# USB.net
KiCad netlist of a schematic drawn in Altium Designer
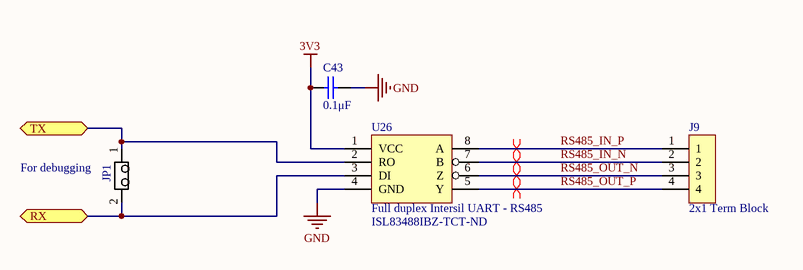
[diagram p0: USB.SchDoc]

(export (version "E")
  (design (tool "Eeschema 10.0.6"))
  (components
    (comp (ref "C43")
      (value "0.1μF")
      (footprint "CAPC1608N(0603\")")
      (description "Capacitor, Ceramic, 100V, +/- 10%, 0603 SMD, X7R")
      (fields
        (field (name "MFG") "TDK")
        (field (name "PUBLISHER") "AUVic")
        (field (name "CREATED BY") "Ashwin Sira")
      )
      (libsource (lib "AUVic_Integrated_Library_Capacitors") (part "0.1uF 100V 0603 SMD, Ceramic"))
    )
    (comp (ref "J9")
      (value "2x1 Term Block")
      (footprint "4X1 Terminal Block")
      (fields (field (name "MADE BY") "Andy Bates"))
      (libsource (lib "AUVic_Integrated_Library_Connectors") (part "4x1 Terminal Block"))
    )
    (comp (ref "JP1")
      (value "1X2 Pin Head")
      (footprint "2X1 Males Header")
      (fields (field (name "MADE BY") "Andy Bates"))
      (libsource (lib "AUVic_Schematic_Library_Connectors") (part "1x2 Male Header"))
    )
    (comp (ref "U26")
      (value "Full duplex Intersil UART - RS485")
      (footprint "SOIC-SN8_M")
      (fields
        (field (name "SUPPLIER PART NUMBER 1") "ISL83488IBZ-TCT-ND")
        (field (name "MADE BY") "Andy Bates")
      )
      (libsource (lib "AUVic_Integrated_Library_Interface") (part "Full duplex Intersil UART - RS485"))
    )
  )
  (nets
    (net (code "1") (name "/RS485_IN_N") (class "Default")
      (node (ref "J9") (pin "2") (pinfunction "2_2") (pintype "passive"))
      (node (ref "U26") (pin "7") (pinfunction "B_7") (pintype "passive"))
    )
    (net (code "2") (name "/RS485_IN_P") (class "Default")
      (node (ref "J9") (pin "1") (pinfunction "1_1") (pintype "passive"))
      (node (ref "U26") (pin "8") (pinfunction "A_8") (pintype "passive"))
    )
    (net (code "3") (name "/RS485_OUT_N") (class "Default")
      (node (ref "J9") (pin "3") (pinfunction "3_3") (pintype "passive"))
      (node (ref "U26") (pin "6") (pinfunction "Z_6") (pintype "passive"))
    )
    (net (code "4") (name "/RS485_OUT_P") (class "Default")
      (node (ref "J9") (pin "4") (pinfunction "4_4") (pintype "passive"))
      (node (ref "U26") (pin "5") (pinfunction "Y_5") (pintype "passive"))
    )
    (net (code "5") (name "/RX") (class "Default")
      (node (ref "JP1") (pin "2") (pinfunction "2_2") (pintype "passive"))
      (node (ref "U26") (pin "3") (pinfunction "DI_3") (pintype "passive"))
    )
    (net (code "6") (name "/TX") (class "Default")
      (node (ref "JP1") (pin "1") (pinfunction "1_1") (pintype "passive"))
      (node (ref "U26") (pin "2") (pinfunction "RO_2") (pintype "passive"))
    )
    (net (code "7") (name "3V3") (class "Default")
      (node (ref "C43") (pin "2") (pinfunction "Cathode_2") (pintype "passive"))
      (node (ref "U26") (pin "1") (pinfunction "VCC_1") (pintype "passive"))
    )
    (net (code "8") (name "GND") (class "Default")
      (node (ref "C43") (pin "1") (pinfunction "Anode_1") (pintype "passive"))
      (node (ref "U26") (pin "4") (pinfunction "GND_4") (pintype "passive"))
    )
  )
)
